# Sheet_prototype.net
KiCad netlist of a schematic drawn in Altium Designer
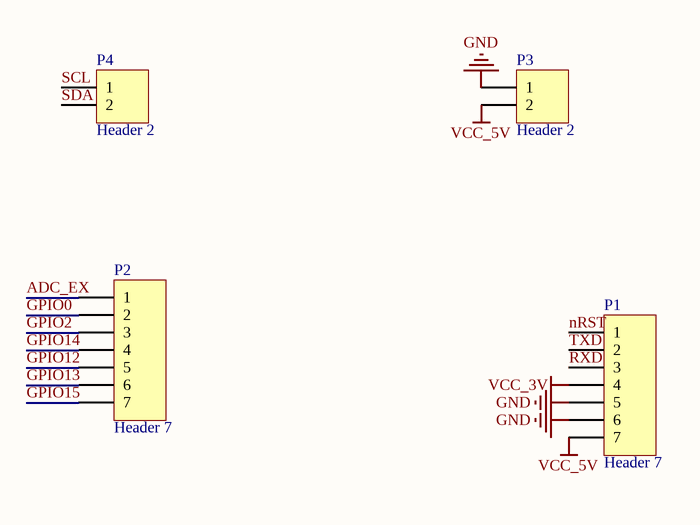
[diagram p0: Sheet_prototype.SchDoc]

(export (version "E")
  (design (tool "Eeschema 10.0.6"))
  (components
    (comp (ref "P1")
      (value "Header 7")
      (footprint "HDR1X7")
      (description "Header, 7-Pin")
      (fields (field (name "PUBLISHER") "Altium Limited"))
      (libsource (lib "Miscellaneous Connectors") (part "Header 7"))
    )
    (comp (ref "P2")
      (value "Header 7")
      (footprint "HDR1X7")
      (description "Header, 7-Pin")
      (fields (field (name "PUBLISHER") "Altium Limited"))
      (libsource (lib "Miscellaneous Connectors") (part "Header 7"))
    )
    (comp (ref "P3")
      (value "Header 2")
      (footprint "HDR1X2")
      (description "Header, 2-Pin")
      (fields (field (name "PUBLISHER") "Altium Limited"))
      (libsource (lib "Miscellaneous Connectors") (part "Header 2"))
    )
    (comp (ref "P4")
      (value "Header 2")
      (footprint "HDR1X2")
      (description "Header, 2-Pin")
      (fields (field (name "PUBLISHER") "Altium Limited"))
      (libsource (lib "Miscellaneous Connectors") (part "Header 2"))
    )
  )
  (nets
    (net (code "1") (name "/ADC_EX") (class "Default")
      (node (ref "P2") (pin "1") (pinfunction "1_1") (pintype "passive"))
    )
    (net (code "2") (name "/GPIO0") (class "Default")
      (node (ref "P2") (pin "2") (pinfunction "2_2") (pintype "passive"))
    )
    (net (code "3") (name "/GPIO2") (class "Default")
      (node (ref "P2") (pin "3") (pinfunction "3_3") (pintype "passive"))
    )
    (net (code "4") (name "/GPIO12") (class "Default")
      (node (ref "P2") (pin "5") (pinfunction "5_5") (pintype "passive"))
    )
    (net (code "5") (name "/GPIO13") (class "Default")
      (node (ref "P2") (pin "6") (pinfunction "6_6") (pintype "passive"))
    )
    (net (code "6") (name "/GPIO14") (class "Default")
      (node (ref "P2") (pin "4") (pinfunction "4_4") (pintype "passive"))
    )
    (net (code "7") (name "/GPIO15") (class "Default")
      (node (ref "P2") (pin "7") (pinfunction "7_7") (pintype "passive"))
    )
    (net (code "8") (name "/RXD") (class "Default")
      (node (ref "P1") (pin "3") (pinfunction "3_3") (pintype "passive"))
    )
    (net (code "9") (name "/SCL") (class "Default")
      (node (ref "P4") (pin "1") (pinfunction "1_1") (pintype "passive"))
    )
    (net (code "10") (name "/SDA") (class "Default")
      (node (ref "P4") (pin "2") (pinfunction "2_2") (pintype "passive"))
    )
    (net (code "11") (name "/TXD") (class "Default")
      (node (ref "P1") (pin "2") (pinfunction "2_2") (pintype "passive"))
    )
    (net (code "12") (name "/nRST") (class "Default")
      (node (ref "P1") (pin "1") (pinfunction "1_1") (pintype "passive"))
    )
    (net (code "13") (name "GND") (class "Default")
      (node (ref "P1") (pin "5") (pinfunction "5_5") (pintype "passive"))
      (node (ref "P1") (pin "6") (pinfunction "6_6") (pintype "passive"))
      (node (ref "P3") (pin "1") (pinfunction "1_1") (pintype "passive"))
    )
    (net (code "14") (name "VCC_3V") (class "Default")
      (node (ref "P1") (pin "4") (pinfunction "4_4") (pintype "passive"))
    )
    (net (code "15") (name "VCC_5V") (class "Default")
      (node (ref "P1") (pin "7") (pinfunction "7_7") (pintype "passive"))
      (node (ref "P3") (pin "2") (pinfunction "2_2") (pintype "passive"))
    )
  )
)
